# esc_control_2.net
KiCad netlist of a schematic drawn in EAGLE
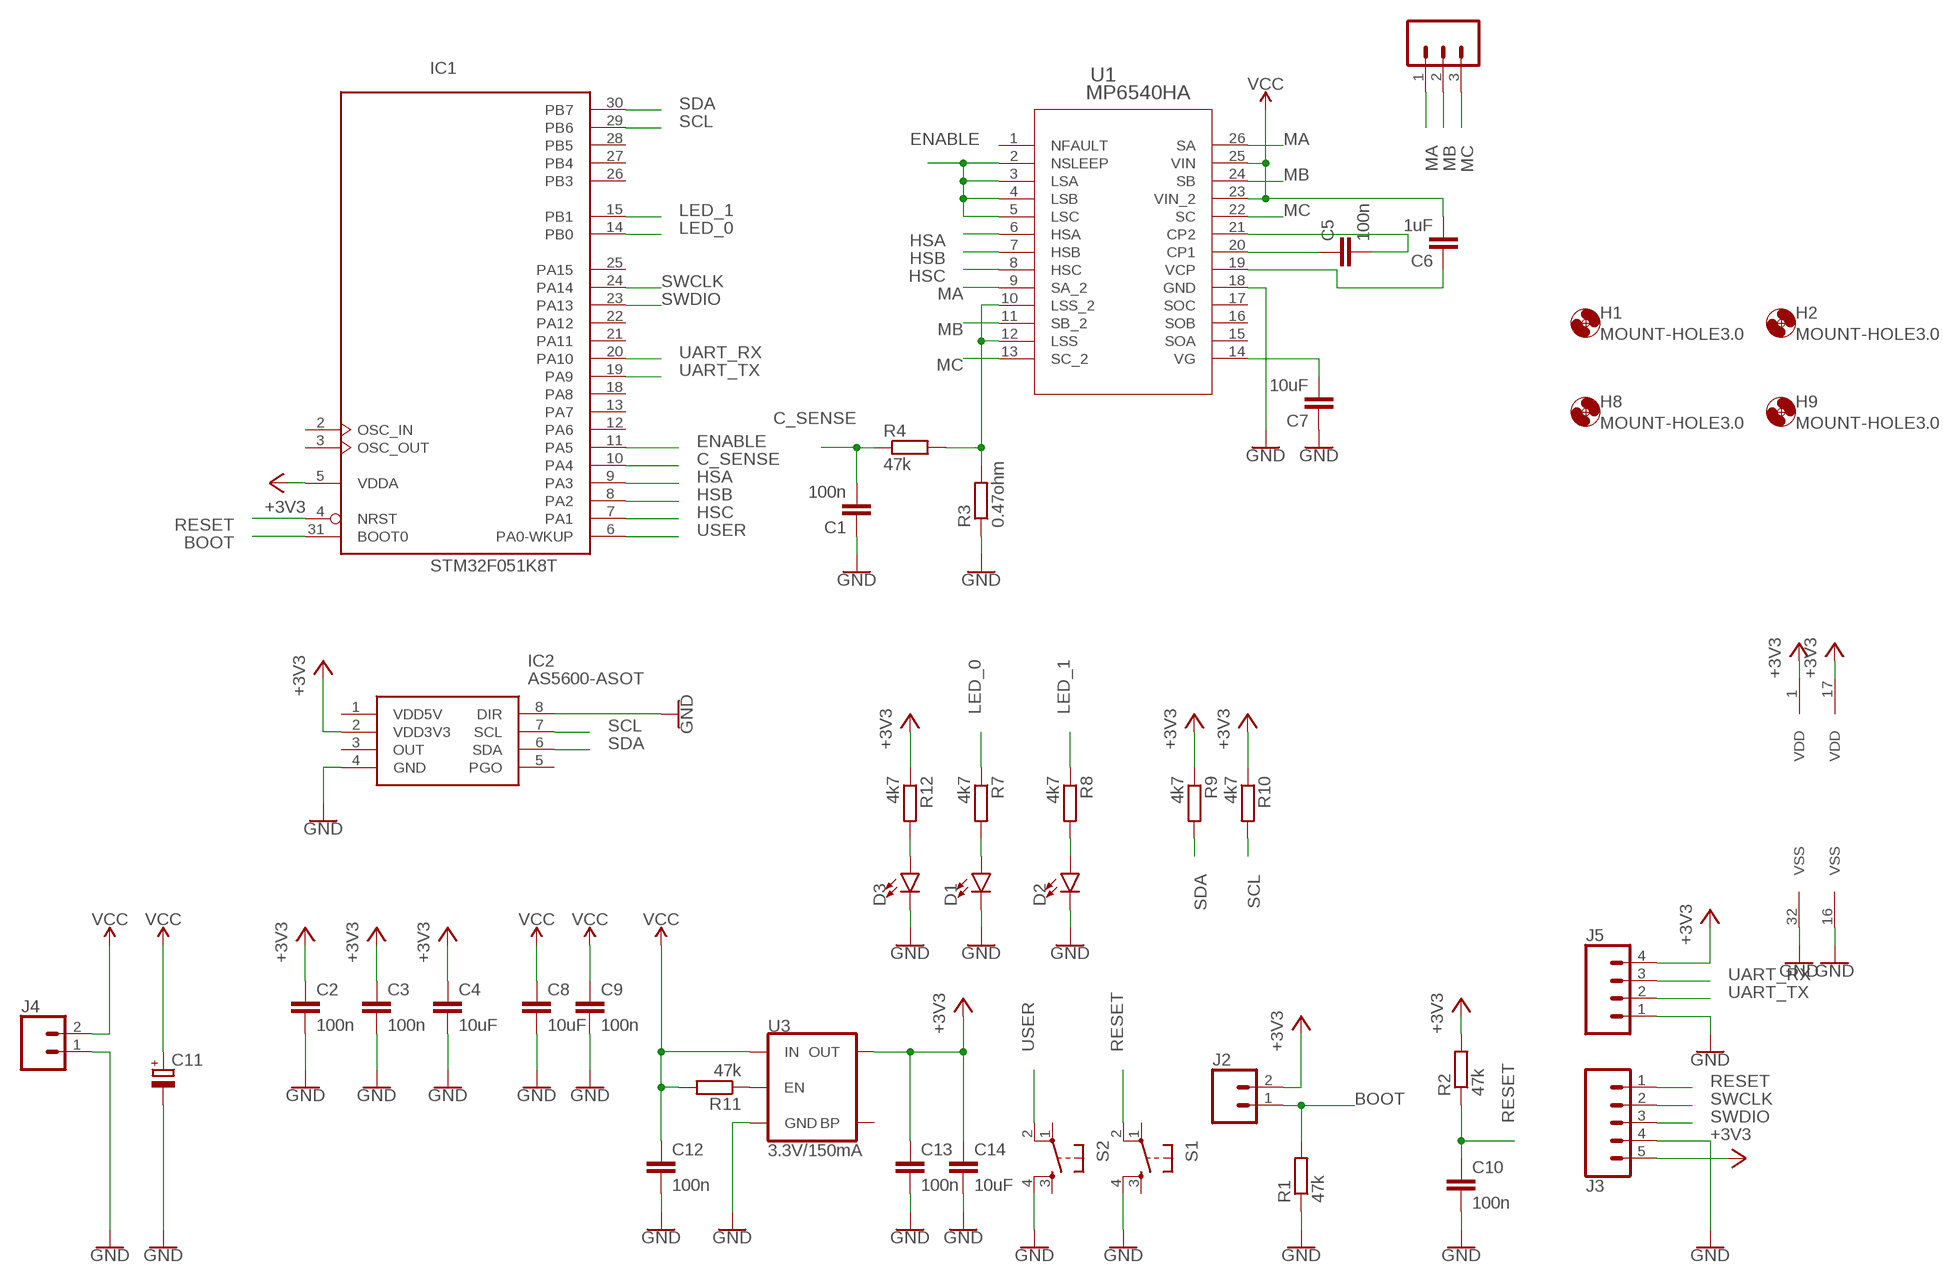
[diagram p0: schematic, sheet 1]

(export (version "E")
  (design (tool "Eeschema 10.0.6"))
  (components
    (comp (ref "C1")
      (value "100n")
      (footprint "eagle-import:C0805")
      (libsource (lib "eagle-import") (part "C-EUC0805"))
    )
    (comp (ref "C2")
      (value "100n")
      (footprint "eagle-import:C0805")
      (libsource (lib "eagle-import") (part "C-EUC0805"))
    )
    (comp (ref "C3")
      (value "100n")
      (footprint "eagle-import:C0805")
      (libsource (lib "eagle-import") (part "C-EUC0805"))
    )
    (comp (ref "C4")
      (value "10uF")
      (footprint "eagle-import:C0805")
      (libsource (lib "eagle-import") (part "C-EUC0805"))
    )
    (comp (ref "C5")
      (value "100n")
      (footprint "eagle-import:C0805")
      (libsource (lib "eagle-import") (part "C-EUC0805"))
    )
    (comp (ref "C6")
      (value "1uF")
      (footprint "eagle-import:C0805")
      (libsource (lib "eagle-import") (part "C-EUC0805"))
    )
    (comp (ref "C7")
      (value "10uF")
      (footprint "eagle-import:C0805")
      (libsource (lib "eagle-import") (part "C-EUC0805"))
    )
    (comp (ref "C8")
      (value "10uF")
      (footprint "eagle-import:C0805")
      (libsource (lib "eagle-import") (part "C-EUC0805"))
    )
    (comp (ref "C9")
      (value "100n")
      (footprint "eagle-import:C0805")
      (libsource (lib "eagle-import") (part "C-EUC0805"))
    )
    (comp (ref "C10")
      (value "100n")
      (footprint "eagle-import:C0805")
      (libsource (lib "eagle-import") (part "C-EUC0805"))
    )
    (comp (ref "C11")
      (value "CPOL-EU153CLV-0605")
      (footprint "eagle-import:153CLV-0605")
      (libsource (lib "eagle-import") (part "CPOL-EU153CLV-0605"))
    )
    (comp (ref "C12")
      (value "100n")
      (footprint "eagle-import:C0805")
      (libsource (lib "eagle-import") (part "C-EUC0805"))
    )
    (comp (ref "C13")
      (value "100n")
      (footprint "eagle-import:C0805")
      (libsource (lib "eagle-import") (part "C-EUC0805"))
    )
    (comp (ref "C14")
      (value "10uF")
      (footprint "eagle-import:C0805")
      (libsource (lib "eagle-import") (part "C-EUC0805"))
    )
    (comp (ref "D1")
      (value "LED1206")
      (footprint "eagle-import:LED-1206")
      (libsource (lib "eagle-import") (part "LED1206"))
    )
    (comp (ref "D2")
      (value "LED1206")
      (footprint "eagle-import:LED-1206")
      (libsource (lib "eagle-import") (part "LED1206"))
    )
    (comp (ref "D3")
      (value "LED1206")
      (footprint "eagle-import:LED-1206")
      (libsource (lib "eagle-import") (part "LED1206"))
    )
    (comp (ref "H1")
      (value "MOUNT-HOLE3.0")
      (footprint "eagle-import:3,0")
      (libsource (lib "eagle-import") (part "MOUNT-HOLE3.0"))
    )
    (comp (ref "H2")
      (value "MOUNT-HOLE3.0")
      (footprint "eagle-import:3,0")
      (libsource (lib "eagle-import") (part "MOUNT-HOLE3.0"))
    )
    (comp (ref "H8")
      (value "MOUNT-HOLE3.0")
      (footprint "eagle-import:3,0")
      (libsource (lib "eagle-import") (part "MOUNT-HOLE3.0"))
    )
    (comp (ref "H9")
      (value "MOUNT-HOLE3.0")
      (footprint "eagle-import:3,0")
      (libsource (lib "eagle-import") (part "MOUNT-HOLE3.0"))
    )
    (comp (ref "IC1")
      (value "STM32F051K8T")
      (footprint "eagle-import:LQFP32")
      (libsource (lib "eagle-import") (part "STM32F051KT8"))
    )
    (comp (ref "IC2")
      (value "AS5600-ASOT")
      (footprint "eagle-import:SOIC127P600X175-8N")
      (fields (field (name "MOUSER_PART_NUMBER") "985-AS5600-ASOT"))
      (libsource (lib "eagle-import") (part "AS5600-ASOT"))
    )
    (comp (ref "J1")
      (value "455-1750-1-ND")
      (footprint "eagle-import:1X03")
      (libsource (lib "eagle-import") (part "CONN_03"))
    )
    (comp (ref "J2")
      (value "CONN_02PTH3")
      (footprint "eagle-import:1X02_LONGPADS")
      (libsource (lib "eagle-import") (part "CONN_02PTH3"))
    )
    (comp (ref "J3")
      (value "CONN_05PTH_LONGPADS")
      (footprint "eagle-import:1X05_LONGPADS")
      (libsource (lib "eagle-import") (part "CONN_05PTH_LONGPADS"))
    )
    (comp (ref "J4")
      (value "CONN_02PTH3")
      (footprint "eagle-import:1X02_LONGPADS")
      (libsource (lib "eagle-import") (part "CONN_02PTH3"))
    )
    (comp (ref "J5")
      (value "CONN_04LONGPADS")
      (footprint "eagle-import:1X04_LONGPADS")
      (libsource (lib "eagle-import") (part "CONN_04LONGPADS"))
    )
    (comp (ref "R1")
      (value "47k")
      (footprint "eagle-import:M0805")
      (libsource (lib "eagle-import") (part "R-EU_M0805"))
    )
    (comp (ref "R2")
      (value "47k")
      (footprint "eagle-import:M0805")
      (libsource (lib "eagle-import") (part "R-EU_M0805"))
    )
    (comp (ref "R3")
      (value "0.47ohm")
      (footprint "eagle-import:R2512")
      (libsource (lib "eagle-import") (part "R-EU_R2512"))
    )
    (comp (ref "R4")
      (value "47k")
      (footprint "eagle-import:M0805")
      (libsource (lib "eagle-import") (part "R-EU_M0805"))
    )
    (comp (ref "R7")
      (value "4k7")
      (footprint "eagle-import:M0805")
      (libsource (lib "eagle-import") (part "R-EU_M0805"))
    )
    (comp (ref "R8")
      (value "4k7")
      (footprint "eagle-import:M0805")
      (libsource (lib "eagle-import") (part "R-EU_M0805"))
    )
    (comp (ref "R9")
      (value "4k7")
      (footprint "eagle-import:M0805")
      (libsource (lib "eagle-import") (part "R-EU_M0805"))
    )
    (comp (ref "R10")
      (value "4k7")
      (footprint "eagle-import:M0805")
      (libsource (lib "eagle-import") (part "R-EU_M0805"))
    )
    (comp (ref "R11")
      (value "47k")
      (footprint "eagle-import:M0805")
      (libsource (lib "eagle-import") (part "R-EU_M0805"))
    )
    (comp (ref "R12")
      (value "4k7")
      (footprint "eagle-import:M0805")
      (libsource (lib "eagle-import") (part "R-EU_M0805"))
    )
    (comp (ref "S1")
      (value "TAC_SWITCHSMD")
      (footprint "eagle-import:TACTILE-SWITCH-SMD")
      (libsource (lib "eagle-import") (part "TAC_SWITCHSMD"))
    )
    (comp (ref "S2")
      (value "TAC_SWITCHSMD")
      (footprint "eagle-import:TACTILE-SWITCH-SMD")
      (libsource (lib "eagle-import") (part "TAC_SWITCHSMD"))
    )
    (comp (ref "U1")
      (value "MP6540HA")
      (footprint "eagle-import:QFN-5X5_MP6540HA_MNP")
      (fields (field (name "COPYRIGHT") "Copyright (C) 2018 Accelerated Designs. All rights reserved"))
      (libsource (lib "eagle-import") (part "MP6540HA"))
    )
    (comp (ref "U3")
      (value "3.3V/150mA")
      (footprint "eagle-import:SOT23-5")
      (libsource (lib "eagle-import") (part "V_REG_MIC52053.3V"))
    )
  )
  (nets
    (net (code "1") (name "+3V3") (class "Default")
      (node (ref "C13") (pin "1") (pinfunction "1_1") (pintype "passive"))
      (node (ref "C14") (pin "1") (pinfunction "1_1") (pintype "passive"))
      (node (ref "C2") (pin "1") (pinfunction "1_1") (pintype "passive"))
      (node (ref "C3") (pin "1") (pinfunction "1_1") (pintype "passive"))
      (node (ref "C4") (pin "1") (pinfunction "1_1") (pintype "passive"))
      (node (ref "IC1") (pin "1") (pinfunction "VDD_1") (pintype "power_in"))
      (node (ref "IC1") (pin "17") (pinfunction "VDD_17") (pintype "power_in"))
      (node (ref "IC1") (pin "5") (pinfunction "VDDA_5") (pintype "power_in"))
      (node (ref "IC2") (pin "2") (pinfunction "VDD3V3_2") (pintype "bidirectional"))
      (node (ref "J2") (pin "2") (pinfunction "2_2") (pintype "passive"))
      (node (ref "J3") (pin "5") (pinfunction "5_5") (pintype "passive"))
      (node (ref "J5") (pin "4") (pinfunction "4_4") (pintype "passive"))
      (node (ref "R10") (pin "1") (pinfunction "1_1") (pintype "passive"))
      (node (ref "R12") (pin "1") (pinfunction "1_1") (pintype "passive"))
      (node (ref "R2") (pin "2") (pinfunction "2_2") (pintype "passive"))
      (node (ref "R9") (pin "1") (pinfunction "1_1") (pintype "passive"))
      (node (ref "U3") (pin "5") (pinfunction "OUT_5") (pintype "passive"))
    )
    (net (code "2") (name "/BOOT") (class "Default")
      (node (ref "IC1") (pin "31") (pinfunction "BOOT0_31") (pintype "input"))
      (node (ref "J2") (pin "1") (pinfunction "1_1") (pintype "passive"))
      (node (ref "R1") (pin "2") (pinfunction "2_2") (pintype "passive"))
    )
    (net (code "3") (name "/C_SENSE") (class "Default")
      (node (ref "C1") (pin "2") (pinfunction "2_2") (pintype "passive"))
      (node (ref "IC1") (pin "10") (pinfunction "PA4_10") (pintype "bidirectional"))
      (node (ref "R4") (pin "1") (pinfunction "1_1") (pintype "passive"))
    )
    (net (code "4") (name "/ENABLE") (class "Default")
      (node (ref "IC1") (pin "11") (pinfunction "PA5_11") (pintype "bidirectional"))
      (node (ref "U1") (pin "2") (pinfunction "NSLEEP_2") (pintype "input"))
      (node (ref "U1") (pin "3") (pinfunction "LSA_3") (pintype "passive"))
      (node (ref "U1") (pin "4") (pinfunction "LSB_4") (pintype "passive"))
      (node (ref "U1") (pin "5") (pinfunction "LSC_5") (pintype "passive"))
    )
    (net (code "5") (name "/HSA") (class "Default")
      (node (ref "IC1") (pin "9") (pinfunction "PA3_9") (pintype "bidirectional"))
      (node (ref "U1") (pin "6") (pinfunction "HSA_6") (pintype "passive"))
    )
    (net (code "6") (name "/HSB") (class "Default")
      (node (ref "IC1") (pin "8") (pinfunction "PA2_8") (pintype "bidirectional"))
      (node (ref "U1") (pin "7") (pinfunction "HSB_7") (pintype "passive"))
    )
    (net (code "7") (name "/HSC") (class "Default")
      (node (ref "IC1") (pin "7") (pinfunction "PA1_7") (pintype "bidirectional"))
      (node (ref "U1") (pin "8") (pinfunction "HSC_8") (pintype "passive"))
    )
    (net (code "8") (name "/LED_0") (class "Default")
      (node (ref "IC1") (pin "14") (pinfunction "PB0_14") (pintype "bidirectional"))
      (node (ref "R7") (pin "1") (pinfunction "1_1") (pintype "passive"))
    )
    (net (code "9") (name "/LED_1") (class "Default")
      (node (ref "IC1") (pin "15") (pinfunction "PB1_15") (pintype "bidirectional"))
      (node (ref "R8") (pin "1") (pinfunction "1_1") (pintype "passive"))
    )
    (net (code "10") (name "/MA") (class "Default")
      (node (ref "J1") (pin "1") (pinfunction "1_1") (pintype "passive"))
      (node (ref "U1") (pin "26") (pinfunction "SA_26") (pintype "output"))
      (node (ref "U1") (pin "9") (pinfunction "SA_2_9") (pintype "output"))
    )
    (net (code "11") (name "/MB") (class "Default")
      (node (ref "J1") (pin "2") (pinfunction "2_2") (pintype "passive"))
      (node (ref "U1") (pin "11") (pinfunction "SB_2_11") (pintype "output"))
      (node (ref "U1") (pin "24") (pinfunction "SB_24") (pintype "output"))
    )
    (net (code "12") (name "/MC") (class "Default")
      (node (ref "J1") (pin "3") (pinfunction "3_3") (pintype "passive"))
      (node (ref "U1") (pin "13") (pinfunction "SC_2_13") (pintype "output"))
      (node (ref "U1") (pin "22") (pinfunction "SC_22") (pintype "output"))
    )
    (net (code "13") (name "/RESET") (class "Default")
      (node (ref "C10") (pin "1") (pinfunction "1_1") (pintype "passive"))
      (node (ref "IC1") (pin "4") (pinfunction "NRST_4") (pintype "bidirectional"))
      (node (ref "J3") (pin "1") (pinfunction "1_1") (pintype "passive"))
      (node (ref "R2") (pin "1") (pinfunction "1_1") (pintype "passive"))
      (node (ref "S1") (pin "2") (pinfunction "2_2") (pintype "passive"))
    )
    (net (code "14") (name "/SCL") (class "Default")
      (node (ref "IC1") (pin "29") (pinfunction "PB6_29") (pintype "bidirectional"))
      (node (ref "IC2") (pin "7") (pinfunction "SCL_7") (pintype "bidirectional"))
      (node (ref "R10") (pin "2") (pinfunction "2_2") (pintype "passive"))
    )
    (net (code "15") (name "/SDA") (class "Default")
      (node (ref "IC1") (pin "30") (pinfunction "PB7_30") (pintype "bidirectional"))
      (node (ref "IC2") (pin "6") (pinfunction "SDA_6") (pintype "bidirectional"))
      (node (ref "R9") (pin "2") (pinfunction "2_2") (pintype "passive"))
    )
    (net (code "16") (name "/SWCLK") (class "Default")
      (node (ref "IC1") (pin "24") (pinfunction "PA14_24") (pintype "bidirectional"))
      (node (ref "J3") (pin "2") (pinfunction "2_2") (pintype "passive"))
    )
    (net (code "17") (name "/SWDIO") (class "Default")
      (node (ref "IC1") (pin "23") (pinfunction "PA13_23") (pintype "bidirectional"))
      (node (ref "J3") (pin "3") (pinfunction "3_3") (pintype "passive"))
    )
    (net (code "18") (name "/UART_RX") (class "Default")
      (node (ref "IC1") (pin "20") (pinfunction "PA10_20") (pintype "bidirectional"))
      (node (ref "J5") (pin "3") (pinfunction "3_3") (pintype "passive"))
    )
    (net (code "19") (name "/UART_TX") (class "Default")
      (node (ref "IC1") (pin "19") (pinfunction "PA9_19") (pintype "bidirectional"))
      (node (ref "J5") (pin "2") (pinfunction "2_2") (pintype "passive"))
    )
    (net (code "20") (name "/USER") (class "Default")
      (node (ref "IC1") (pin "6") (pinfunction "PA0-WKUP_6") (pintype "bidirectional"))
      (node (ref "S2") (pin "2") (pinfunction "2_2") (pintype "passive"))
    )
    (net (code "21") (name "GND") (class "Default")
      (node (ref "C1") (pin "1") (pinfunction "1_1") (pintype "passive"))
      (node (ref "C10") (pin "2") (pinfunction "2_2") (pintype "passive"))
      (node (ref "C11") (pin "-") (pinfunction "-_-") (pintype "passive"))
      (node (ref "C12") (pin "2") (pinfunction "2_2") (pintype "passive"))
      (node (ref "C13") (pin "2") (pinfunction "2_2") (pintype "passive"))
      (node (ref "C14") (pin "2") (pinfunction "2_2") (pintype "passive"))
      (node (ref "C2") (pin "2") (pinfunction "2_2") (pintype "passive"))
      (node (ref "C3") (pin "2") (pinfunction "2_2") (pintype "passive"))
      (node (ref "C4") (pin "2") (pinfunction "2_2") (pintype "passive"))
      (node (ref "C7") (pin "1") (pinfunction "1_1") (pintype "passive"))
      (node (ref "C8") (pin "2") (pinfunction "2_2") (pintype "passive"))
      (node (ref "C9") (pin "2") (pinfunction "2_2") (pintype "passive"))
      (node (ref "D1") (pin "C") (pinfunction "C_C") (pintype "passive"))
      (node (ref "D2") (pin "C") (pinfunction "C_C") (pintype "passive"))
      (node (ref "D3") (pin "C") (pinfunction "C_C") (pintype "passive"))
      (node (ref "IC1") (pin "16") (pinfunction "VSS_16") (pintype "power_in"))
      (node (ref "IC1") (pin "32") (pinfunction "VSS_32") (pintype "power_in"))
      (node (ref "IC2") (pin "4") (pinfunction "GND_4") (pintype "bidirectional"))
      (node (ref "IC2") (pin "8") (pinfunction "DIR_8") (pintype "bidirectional"))
      (node (ref "J3") (pin "4") (pinfunction "4_4") (pintype "passive"))
      (node (ref "J4") (pin "1") (pinfunction "1_1") (pintype "passive"))
      (node (ref "J5") (pin "1") (pinfunction "1_1") (pintype "passive"))
      (node (ref "R1") (pin "1") (pinfunction "1_1") (pintype "passive"))
      (node (ref "R3") (pin "1") (pinfunction "1_1") (pintype "passive"))
      (node (ref "S1") (pin "4") (pinfunction "4_4") (pintype "passive"))
      (node (ref "S2") (pin "4") (pinfunction "4_4") (pintype "passive"))
      (node (ref "U1") (pin "18") (pinfunction "GND_18") (pintype "passive"))
      (node (ref "U3") (pin "2") (pinfunction "GND_2") (pintype "input"))
    )
    (net (code "22") (name "Net-(D1-PadA)") (class "Default")
      (node (ref "D1") (pin "A") (pinfunction "A_A") (pintype "passive"))
      (node (ref "R7") (pin "2") (pinfunction "2_2") (pintype "passive"))
    )
    (net (code "23") (name "Net-(D2-PadA)") (class "Default")
      (node (ref "D2") (pin "A") (pinfunction "A_A") (pintype "passive"))
      (node (ref "R8") (pin "2") (pinfunction "2_2") (pintype "passive"))
    )
    (net (code "24") (name "Net-(D3-PadA)") (class "Default")
      (node (ref "D3") (pin "A") (pinfunction "A_A") (pintype "passive"))
      (node (ref "R12") (pin "2") (pinfunction "2_2") (pintype "passive"))
    )
    (net (code "25") (name "Net-(U1-CP1)") (class "Default")
      (node (ref "C5") (pin "1") (pinfunction "1_1") (pintype "passive"))
      (node (ref "U1") (pin "20") (pinfunction "CP1_20") (pintype "passive"))
    )
    (net (code "26") (name "Net-(U1-CP2)") (class "Default")
      (node (ref "C5") (pin "2") (pinfunction "2_2") (pintype "passive"))
      (node (ref "U1") (pin "21") (pinfunction "CP2_21") (pintype "passive"))
    )
    (net (code "27") (name "Net-(U1-LSS)") (class "Default")
      (node (ref "R3") (pin "2") (pinfunction "2_2") (pintype "passive"))
      (node (ref "R4") (pin "2") (pinfunction "2_2") (pintype "passive"))
      (node (ref "U1") (pin "10") (pinfunction "LSS_2_10") (pintype "passive"))
      (node (ref "U1") (pin "12") (pinfunction "LSS_12") (pintype "passive"))
    )
    (net (code "28") (name "Net-(U1-VCP)") (class "Default")
      (node (ref "C6") (pin "1") (pinfunction "1_1") (pintype "passive"))
      (node (ref "U1") (pin "19") (pinfunction "VCP_19") (pintype "output"))
    )
    (net (code "29") (name "Net-(U1-VG)") (class "Default")
      (node (ref "C7") (pin "2") (pinfunction "2_2") (pintype "passive"))
      (node (ref "U1") (pin "14") (pinfunction "VG_14") (pintype "power_in"))
    )
    (net (code "30") (name "Net-(U3-EN)") (class "Default")
      (node (ref "R11") (pin "1") (pinfunction "1_1") (pintype "passive"))
      (node (ref "U3") (pin "3") (pinfunction "EN_3") (pintype "input"))
    )
    (net (code "31") (name "VCC") (class "Default")
      (node (ref "C11") (pin "+") (pinfunction "+_+") (pintype "passive"))
      (node (ref "C12") (pin "1") (pinfunction "1_1") (pintype "passive"))
      (node (ref "C6") (pin "2") (pinfunction "2_2") (pintype "passive"))
      (node (ref "C8") (pin "1") (pinfunction "1_1") (pintype "passive"))
      (node (ref "C9") (pin "1") (pinfunction "1_1") (pintype "passive"))
      (node (ref "J4") (pin "2") (pinfunction "2_2") (pintype "passive"))
      (node (ref "R11") (pin "2") (pinfunction "2_2") (pintype "passive"))
      (node (ref "U1") (pin "23") (pinfunction "VIN_2_23") (pintype "power_in"))
      (node (ref "U1") (pin "25") (pinfunction "VIN_25") (pintype "power_in"))
      (node (ref "U3") (pin "1") (pinfunction "IN_1") (pintype "input"))
    )
    (net (code "32") (name "unconnected-(IC1A-OSC_IN-Pad2)") (class "Default")
      (node (ref "IC1") (pin "2") (pinfunction "OSC_IN_2") (pintype "bidirectional"))
    )
    (net (code "33") (name "unconnected-(IC1A-OSC_OUT-Pad3)") (class "Default")
      (node (ref "IC1") (pin "3") (pinfunction "OSC_OUT_3") (pintype "bidirectional"))
    )
    (net (code "34") (name "unconnected-(IC1A-PA6-Pad12)") (class "Default")
      (node (ref "IC1") (pin "12") (pinfunction "PA6_12") (pintype "bidirectional"))
    )
    (net (code "35") (name "unconnected-(IC1A-PA7-Pad13)") (class "Default")
      (node (ref "IC1") (pin "13") (pinfunction "PA7_13") (pintype "bidirectional"))
    )
    (net (code "36") (name "unconnected-(IC1A-PA8-Pad18)") (class "Default")
      (node (ref "IC1") (pin "18") (pinfunction "PA8_18") (pintype "bidirectional"))
    )
    (net (code "37") (name "unconnected-(IC1A-PA11-Pad21)") (class "Default")
      (node (ref "IC1") (pin "21") (pinfunction "PA11_21") (pintype "bidirectional"))
    )
    (net (code "38") (name "unconnected-(IC1A-PA12-Pad22)") (class "Default")
      (node (ref "IC1") (pin "22") (pinfunction "PA12_22") (pintype "bidirectional"))
    )
    (net (code "39") (name "unconnected-(IC1A-PA15-Pad25)") (class "Default")
      (node (ref "IC1") (pin "25") (pinfunction "PA15_25") (pintype "bidirectional"))
    )
    (net (code "40") (name "unconnected-(IC1A-PB3-Pad26)") (class "Default")
      (node (ref "IC1") (pin "26") (pinfunction "PB3_26") (pintype "bidirectional"))
    )
    (net (code "41") (name "unconnected-(IC1A-PB4-Pad27)") (class "Default")
      (node (ref "IC1") (pin "27") (pinfunction "PB4_27") (pintype "bidirectional"))
    )
    (net (code "42") (name "unconnected-(IC1A-PB5-Pad28)") (class "Default")
      (node (ref "IC1") (pin "28") (pinfunction "PB5_28") (pintype "bidirectional"))
    )
    (net (code "43") (name "unconnected-(IC2-OUT-Pad3)") (class "Default")
      (node (ref "IC2") (pin "3") (pinfunction "OUT_3") (pintype "bidirectional"))
    )
    (net (code "44") (name "unconnected-(IC2-PGO-Pad5)") (class "Default")
      (node (ref "IC2") (pin "5") (pinfunction "PGO_5") (pintype "bidirectional"))
    )
    (net (code "45") (name "unconnected-(IC2-VDD5V-Pad1)") (class "Default")
      (node (ref "IC2") (pin "1") (pinfunction "VDD5V_1") (pintype "bidirectional"))
    )
    (net (code "46") (name "unconnected-(S1-Pad1)") (class "Default")
      (node (ref "S1") (pin "1") (pinfunction "1_1") (pintype "passive"))
    )
    (net (code "47") (name "unconnected-(S1-Pad3)") (class "Default")
      (node (ref "S1") (pin "3") (pinfunction "3_3") (pintype "passive"))
    )
    (net (code "48") (name "unconnected-(S2-Pad1)") (class "Default")
      (node (ref "S2") (pin "1") (pinfunction "1_1") (pintype "passive"))
    )
    (net (code "49") (name "unconnected-(S2-Pad3)") (class "Default")
      (node (ref "S2") (pin "3") (pinfunction "3_3") (pintype "passive"))
    )
    (net (code "50") (name "unconnected-(U1-NFAULT-Pad1)") (class "Default")
      (node (ref "U1") (pin "1") (pinfunction "NFAULT_1") (pintype "output"))
    )
    (net (code "51") (name "unconnected-(U1-SOA-Pad15)") (class "Default")
      (node (ref "U1") (pin "15") (pinfunction "SOA_15") (pintype "output"))
    )
    (net (code "52") (name "unconnected-(U1-SOB-Pad16)") (class "Default")
      (node (ref "U1") (pin "16") (pinfunction "SOB_16") (pintype "output"))
    )
    (net (code "53") (name "unconnected-(U1-SOC-Pad17)") (class "Default")
      (node (ref "U1") (pin "17") (pinfunction "SOC_17") (pintype "output"))
    )
    (net (code "54") (name "unconnected-(U3-BP-Pad4)") (class "Default")
      (node (ref "U3") (pin "4") (pinfunction "BP_4") (pintype "input"))
    )
  )
)
